# modFOC-ESC-Interface.net
KiCad netlist of a schematic drawn in Altium Designer
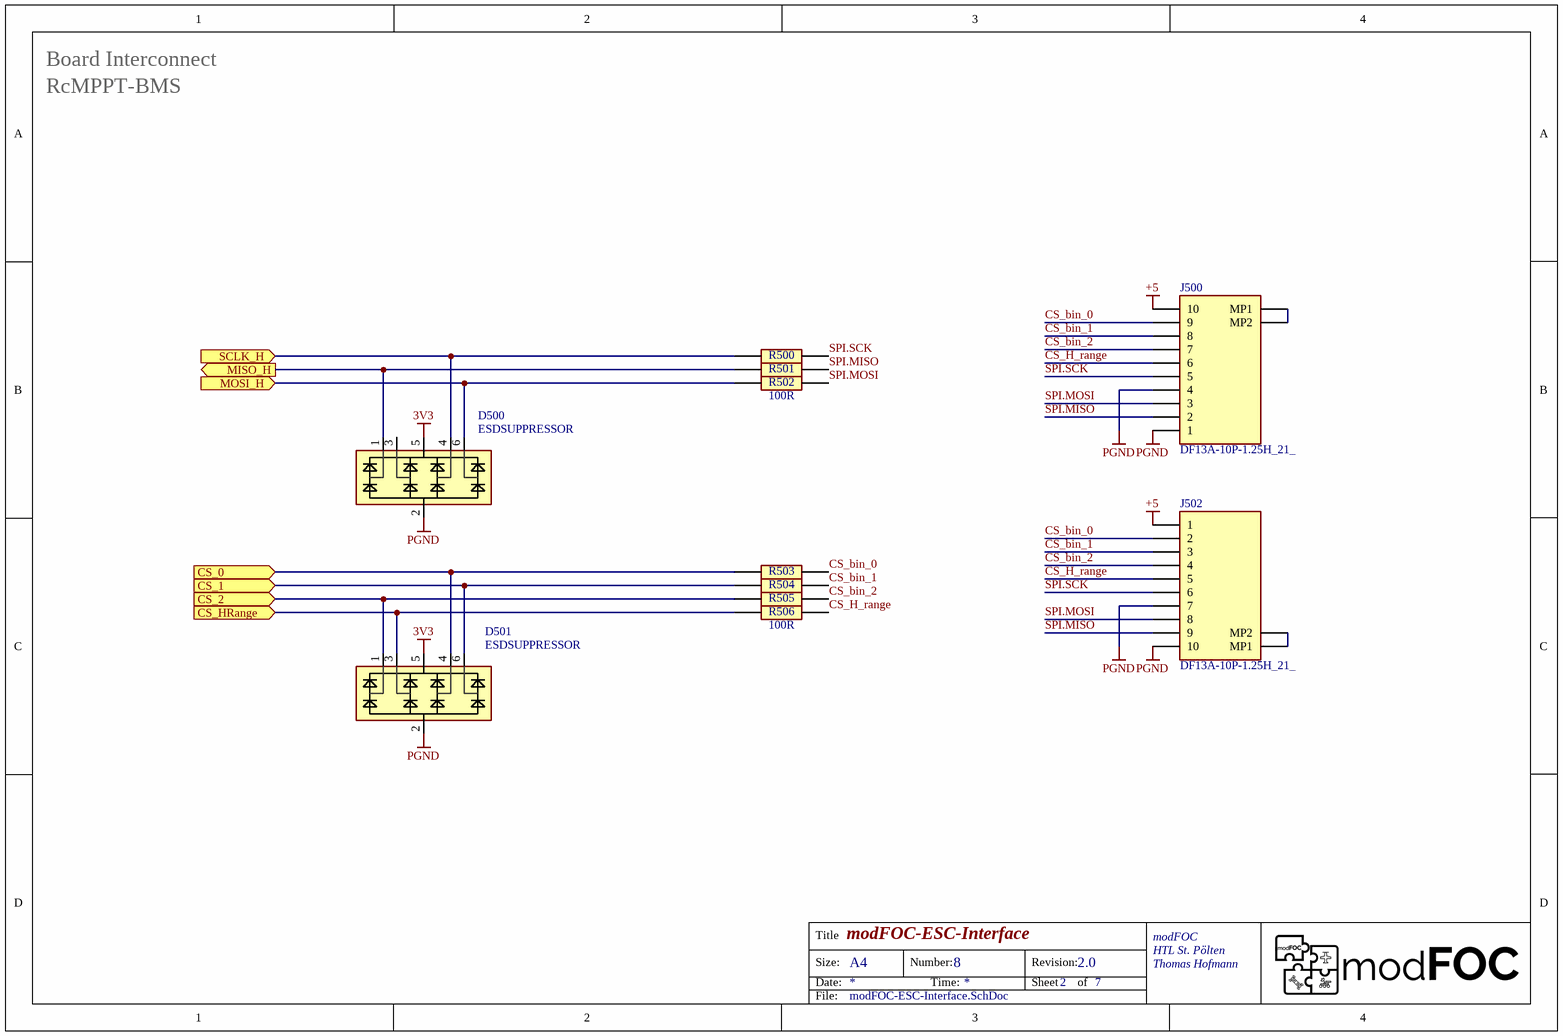
[diagram p0: modFOC-ESC-Interface.SchDoc]

(export (version "E")
  (design (tool "Eeschema 10.0.6"))
  (components
    (comp (ref "D500")
      (value "ESDSUPPRESSOR")
      (footprint "SOT23-6")
      (description "TVS Diode Array")
      (libsource (lib "RcMPPTLib") (part "ESDSUPPRESSOR"))
    )
    (comp (ref "D501")
      (value "ESDSUPPRESSOR")
      (footprint "SOT23-6")
      (description "TVS Diode Array")
      (libsource (lib "RcMPPTLib") (part "ESDSUPPRESSOR"))
    )
    (comp (ref "J500")
      (value "DF13A-10P-1.25H_21_")
      (footprint "DF13A10P125H21")
      (description "10Pin DF13 Connector")
      (fields
        (field (name "MANUFACTURER_PART_NUMBER") "DF13A-10P-1.25H(21)")
        (field (name "MOUSER PART NUMBER") "798-DF13A10P125H21")
      )
      (libsource (lib "Schlib1") (part "DF13A-10P-1.25H_21_"))
    )
    (comp (ref "J502")
      (value "DF13A-10P-1.25H_21_")
      (footprint "DF13A10P125H21")
      (description "10Pin DF13 Connector")
      (fields
        (field (name "MANUFACTURER_PART_NUMBER") "DF13A-10P-1.25H(21)")
        (field (name "MOUSER PART NUMBER") "798-DF13A10P125H21")
      )
      (libsource (lib "") (part "DF13A-10P-1.25H_21__1"))
    )
    (comp (ref "R500")
      (value "100R")
      (footprint "RESC1005X40N")
      (description "Resistor")
      (libsource (lib "RcMPPTLib") (part "R0402"))
    )
    (comp (ref "R501")
      (value "100R")
      (footprint "RESC1005X40N")
      (description "Resistor")
      (libsource (lib "RcMPPTLib") (part "R0402"))
    )
    (comp (ref "R502")
      (value "100R")
      (footprint "RESC1005X40N")
      (description "Resistor")
      (libsource (lib "RcMPPTLib") (part "R0402"))
    )
    (comp (ref "R503")
      (value "100R")
      (footprint "RESC1005X40N")
      (description "Resistor")
      (libsource (lib "RcMPPTLib") (part "R0402"))
    )
    (comp (ref "R504")
      (value "100R")
      (footprint "RESC1005X40N")
      (description "Resistor")
      (libsource (lib "RcMPPTLib") (part "R0402"))
    )
    (comp (ref "R505")
      (value "100R")
      (footprint "RESC1005X40N")
      (description "Resistor")
      (libsource (lib "RcMPPTLib") (part "R0402"))
    )
    (comp (ref "R506")
      (value "100R")
      (footprint "RESC1005X40N")
      (description "Resistor")
      (libsource (lib "RcMPPTLib") (part "R0402"))
    )
  )
  (nets
    (net (code "1") (name "+5") (class "Default")
      (node (ref "J500") (pin "10") (pinfunction "10_10") (pintype "passive"))
      (node (ref "J502") (pin "1") (pinfunction "1_1") (pintype "passive"))
    )
    (net (code "2") (name "/CS_0") (class "Default")
      (node (ref "D501") (pin "4") (pinfunction "CH3_4") (pintype "passive"))
      (node (ref "R503") (pin "1") (pinfunction "1_1") (pintype "passive"))
    )
    (net (code "3") (name "/CS_1") (class "Default")
      (node (ref "D501") (pin "6") (pinfunction "CH4_6") (pintype "passive"))
      (node (ref "R504") (pin "1") (pinfunction "1_1") (pintype "passive"))
    )
    (net (code "4") (name "/CS_2") (class "Default")
      (node (ref "D501") (pin "1") (pinfunction "CH1_1") (pintype "passive"))
      (node (ref "R505") (pin "1") (pinfunction "1_1") (pintype "passive"))
    )
    (net (code "5") (name "/CS_HRange") (class "Default")
      (node (ref "D501") (pin "3") (pinfunction "CH2_3") (pintype "passive"))
      (node (ref "R506") (pin "1") (pinfunction "1_1") (pintype "passive"))
    )
    (net (code "6") (name "/CS_H_range") (class "Default")
      (node (ref "J500") (pin "6") (pinfunction "6_6") (pintype "passive"))
      (node (ref "J502") (pin "5") (pinfunction "5_5") (pintype "passive"))
      (node (ref "R506") (pin "2") (pinfunction "2_2") (pintype "passive"))
    )
    (net (code "7") (name "/CS_bin_0") (class "Default")
      (node (ref "J500") (pin "9") (pinfunction "9_9") (pintype "passive"))
      (node (ref "J502") (pin "2") (pinfunction "2_2") (pintype "passive"))
      (node (ref "R503") (pin "2") (pinfunction "2_2") (pintype "passive"))
    )
    (net (code "8") (name "/CS_bin_1") (class "Default")
      (node (ref "J500") (pin "8") (pinfunction "8_8") (pintype "passive"))
      (node (ref "J502") (pin "3") (pinfunction "3_3") (pintype "passive"))
      (node (ref "R504") (pin "2") (pinfunction "2_2") (pintype "passive"))
    )
    (net (code "9") (name "/CS_bin_2") (class "Default")
      (node (ref "J500") (pin "7") (pinfunction "7_7") (pintype "passive"))
      (node (ref "J502") (pin "4") (pinfunction "4_4") (pintype "passive"))
      (node (ref "R505") (pin "2") (pinfunction "2_2") (pintype "passive"))
    )
    (net (code "10") (name "/MISO_H") (class "Default")
      (node (ref "D500") (pin "1") (pinfunction "CH1_1") (pintype "passive"))
      (node (ref "R501") (pin "1") (pinfunction "1_1") (pintype "passive"))
    )
    (net (code "11") (name "/MOSI_H") (class "Default")
      (node (ref "D500") (pin "6") (pinfunction "CH4_6") (pintype "passive"))
      (node (ref "R502") (pin "1") (pinfunction "1_1") (pintype "passive"))
    )
    (net (code "12") (name "/SCLK_H") (class "Default")
      (node (ref "D500") (pin "4") (pinfunction "CH3_4") (pintype "passive"))
      (node (ref "R500") (pin "1") (pinfunction "1_1") (pintype "passive"))
    )
    (net (code "13") (name "/SPI.MISO") (class "Default")
      (node (ref "J500") (pin "2") (pinfunction "2_2") (pintype "passive"))
      (node (ref "J502") (pin "9") (pinfunction "9_9") (pintype "passive"))
      (node (ref "R501") (pin "2") (pinfunction "2_2") (pintype "passive"))
    )
    (net (code "14") (name "/SPI.MOSI") (class "Default")
      (node (ref "J500") (pin "3") (pinfunction "3_3") (pintype "passive"))
      (node (ref "J502") (pin "8") (pinfunction "8_8") (pintype "passive"))
      (node (ref "R502") (pin "2") (pinfunction "2_2") (pintype "passive"))
    )
    (net (code "15") (name "/SPI.SCK") (class "Default")
      (node (ref "J500") (pin "5") (pinfunction "5_5") (pintype "passive"))
      (node (ref "J502") (pin "6") (pinfunction "6_6") (pintype "passive"))
      (node (ref "R500") (pin "2") (pinfunction "2_2") (pintype "passive"))
    )
    (net (code "16") (name "3V3") (class "Default")
      (node (ref "D500") (pin "5") (pinfunction "VDD_5") (pintype "passive"))
      (node (ref "D501") (pin "5") (pinfunction "VDD_5") (pintype "passive"))
    )
    (net (code "17") (name "Net-(J500-PadMP1)") (class "Default")
      (node (ref "J500") (pin "MP1") (pinfunction "MP1_MP1") (pintype "passive"))
      (node (ref "J500") (pin "MP2") (pinfunction "MP2_MP2") (pintype "passive"))
    )
    (net (code "18") (name "Net-(J502-PadMP1)") (class "Default")
      (node (ref "J502") (pin "MP1") (pinfunction "MP1_MP1") (pintype "passive"))
      (node (ref "J502") (pin "MP2") (pinfunction "MP2_MP2") (pintype "passive"))
    )
    (net (code "19") (name "PGND") (class "Default")
      (node (ref "D500") (pin "2") (pinfunction "GND_2") (pintype "passive"))
      (node (ref "D501") (pin "2") (pinfunction "GND_2") (pintype "passive"))
      (node (ref "J500") (pin "1") (pinfunction "1_1") (pintype "passive"))
      (node (ref "J500") (pin "4") (pinfunction "4_4") (pintype "passive"))
      (node (ref "J502") (pin "10") (pinfunction "10_10") (pintype "passive"))
      (node (ref "J502") (pin "7") (pinfunction "7_7") (pintype "passive"))
    )
    (net (code "20") (name "unconnected-(D500-CH2-Pad3)") (class "Default")
      (node (ref "D500") (pin "3") (pinfunction "CH2_3") (pintype "passive"))
    )
  )
)
